# LIN_Interceptor_Board_EasyEDA_Pro.net
KiCad netlist of a schematic drawn in EasyEDA Pro
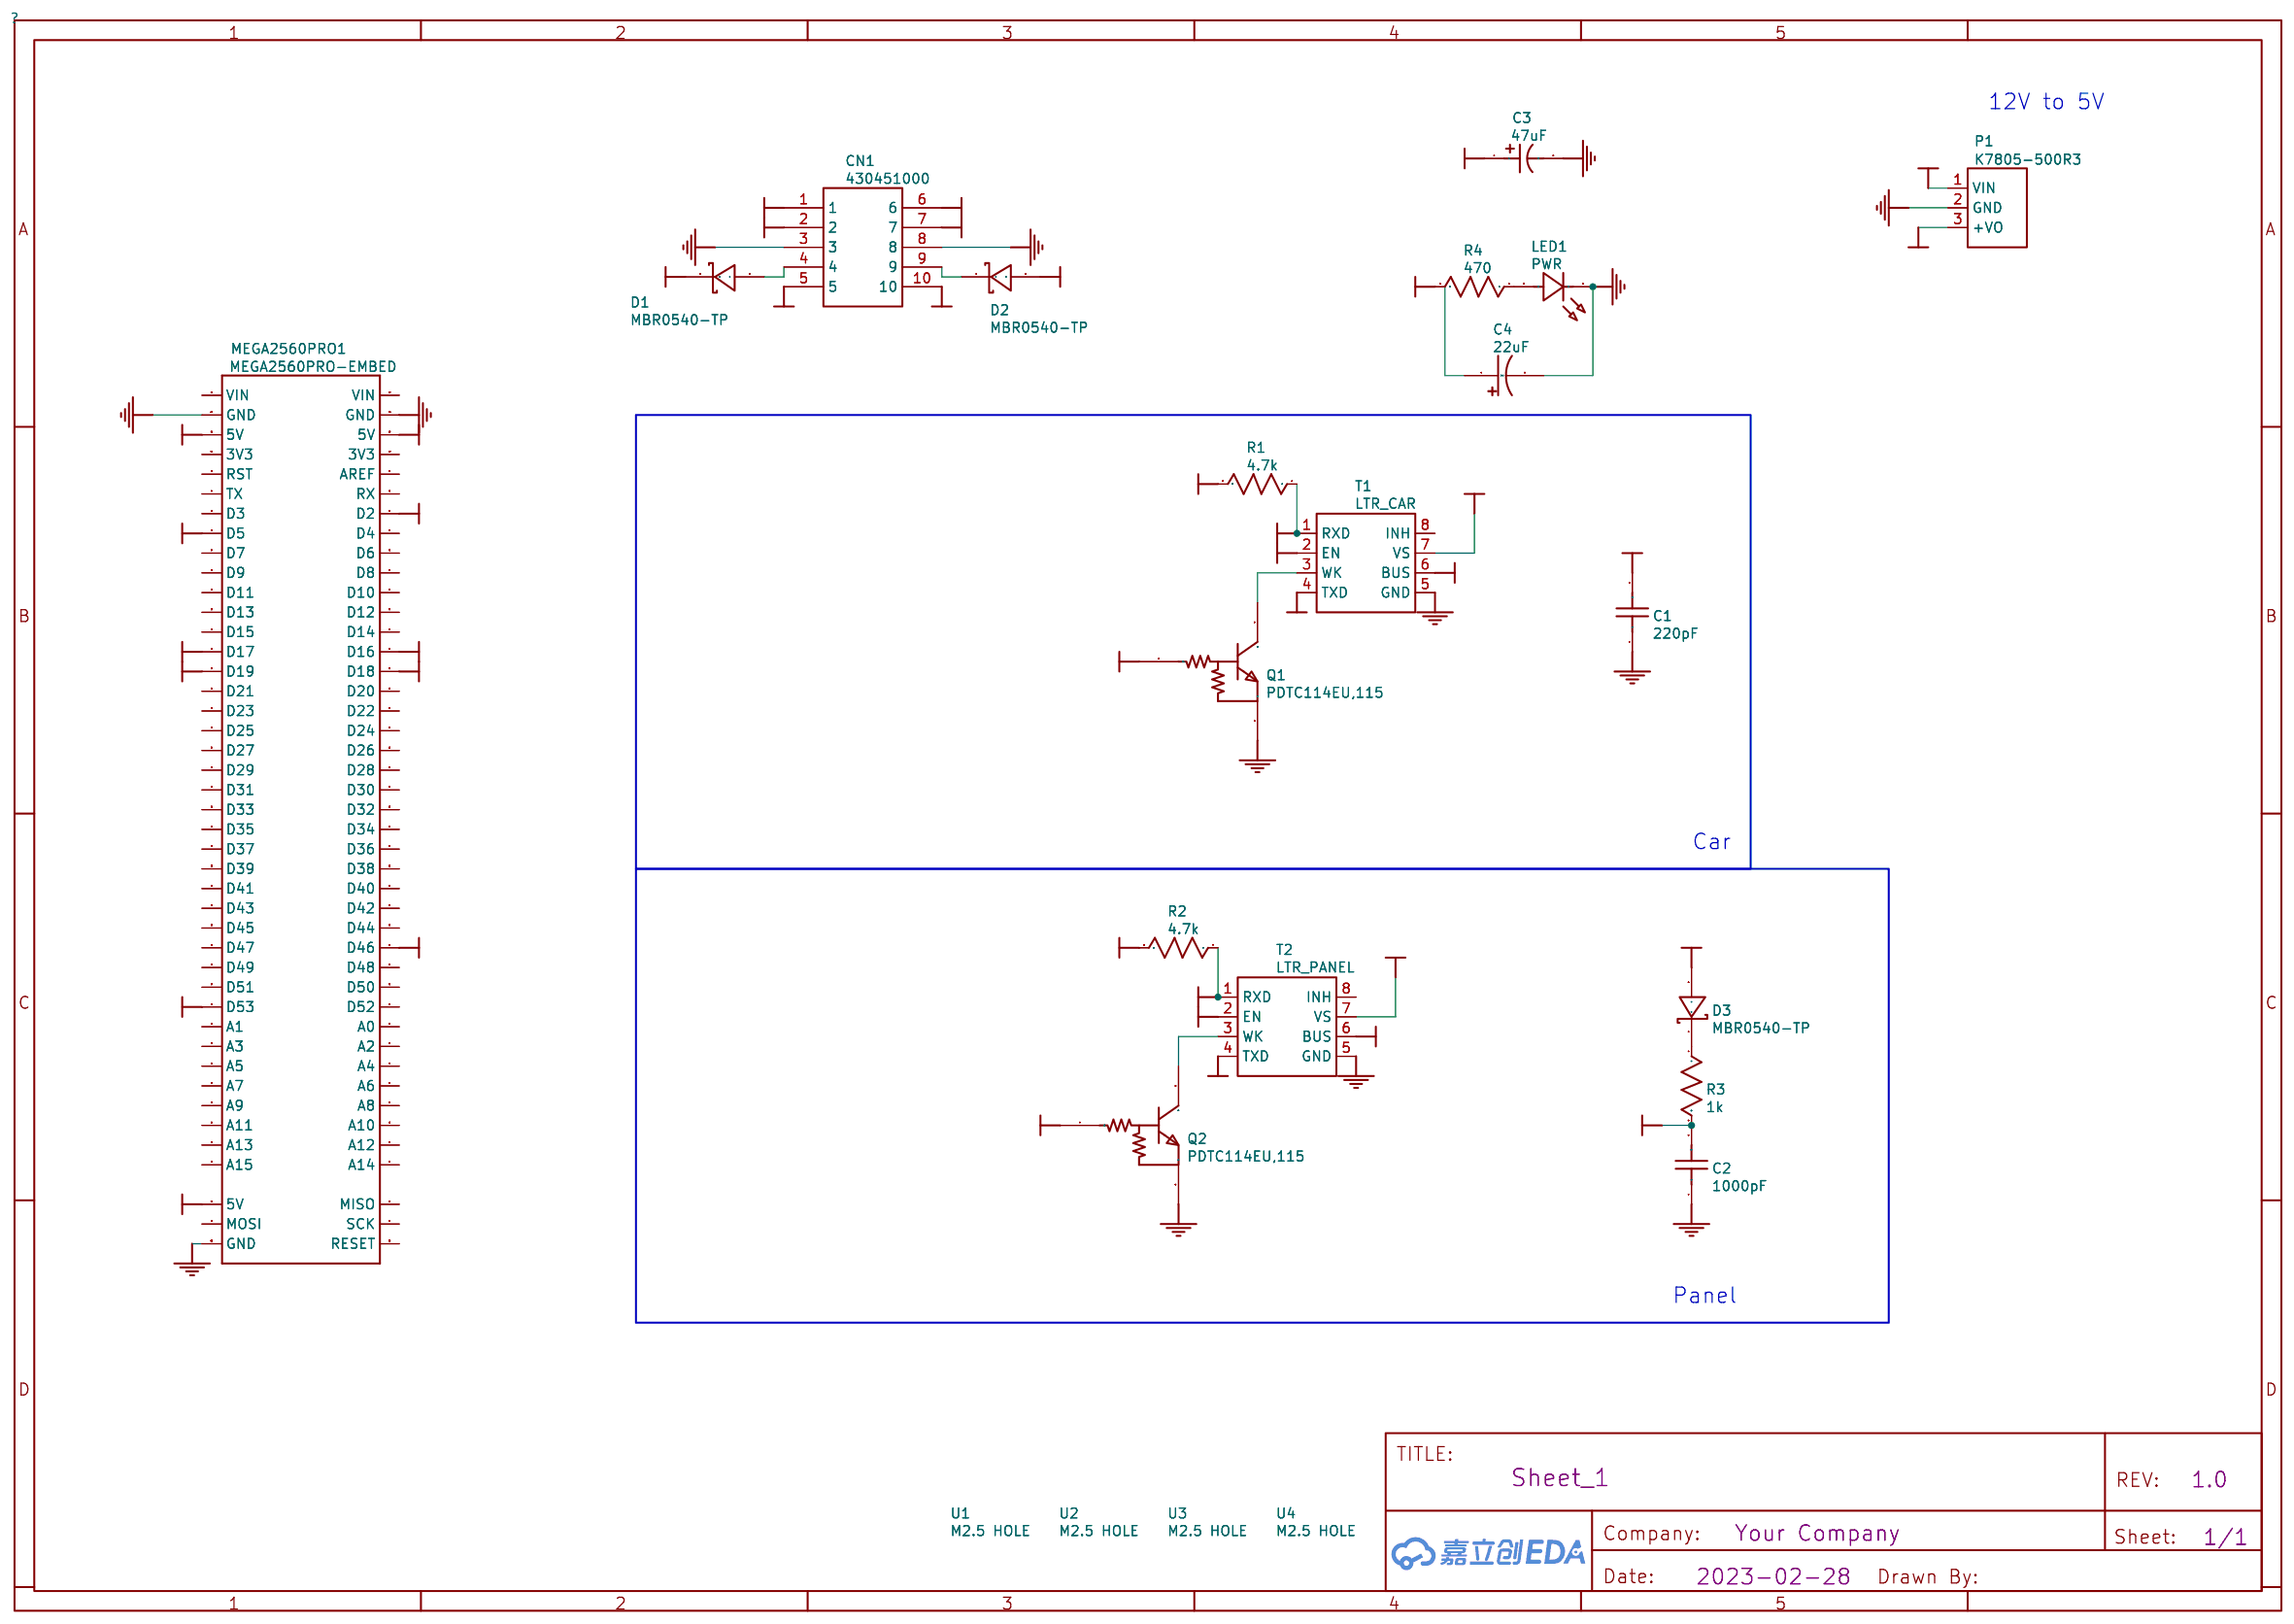
[diagram p0: schematic sheet]

(export (version "E")
  (design (tool "Eeschema 10.0.6"))
  (components
    (comp (ref "C1")
      (value "220pF")
      (footprint "easyedapro:C0603")
      (fields (field (name "Contributor") "LCEDA_Lib"))
      (libsource (lib "easyedapro") (part "220pF"))
    )
    (comp (ref "C2")
      (value "1000pF")
      (footprint "easyedapro:C0603")
      (fields (field (name "Contributor") "LCEDA_Lib"))
      (libsource (lib "easyedapro") (part "1000pF"))
    )
    (comp (ref "C3")
      (value "47uF")
      (footprint "easyedapro:CAP-SMD_BD6.3-L6.6-W6.6-LS7.3-FD")
      (fields
        (field (name "Manufacturer Part") "XT47UF50V90RV0082")
        (field (name "Manufacturer") "KNSCHA(科尼盛)")
        (field (name "Contributor") "lcsc")
      )
      (libsource (lib "easyedapro") (part "47uF"))
    )
    (comp (ref "C4")
      (value "22uF")
      (footprint "easyedapro:CAP-SMD_BD4.0-L4.3-W4.3-LS5.3-FD")
      (fields
        (field (name "Manufacturer Part") "RVT1A220M0405")
        (field (name "Manufacturer") "ROQANG(容强)")
        (field (name "Contributor") "LCSC")
      )
      (libsource (lib "easyedapro") (part "22uF"))
    )
    (comp (ref "CN1")
      (value "430451000")
      (footprint "easyedapro:CONN-TH_43045-1000")
      (fields (field (name "Manufacturer") "MOLEX"))
      (libsource (lib "easyedapro") (part "430451000"))
    )
    (comp (ref "D1")
      (value "MBR0540-TP")
      (footprint "easyedapro:SOD-123_L2.7-W1.6-LS3.7-RD")
      (fields (field (name "Manufacturer") "MCC(美微科)") (field (name "Contributor") "LCSC"))
      (libsource (lib "easyedapro") (part "MBR0540-TP"))
    )
    (comp (ref "D2")
      (value "MBR0540-TP")
      (footprint "easyedapro:SOD-123_L2.7-W1.6-LS3.7-RD")
      (fields (field (name "Manufacturer") "MCC(美微科)") (field (name "Contributor") "LCSC"))
      (libsource (lib "easyedapro") (part "MBR0540-TP"))
    )
    (comp (ref "D3")
      (value "MBR0540-TP")
      (footprint "easyedapro:SOD-123_L2.7-W1.6-LS3.7-RD")
      (fields (field (name "Manufacturer") "MCC(美微科)") (field (name "Contributor") "LCSC"))
      (libsource (lib "easyedapro") (part "MBR0540-TP"))
    )
    (comp (ref "LED1")
      (value "PWR")
      (footprint "easyedapro:LED0603-RD_RED")
      (fields
        (field (name "Manufacturer Part") "L-C191MJRCT")
        (field (name "Manufacturer") "PARALIGHT(光鼎)")
        (field (name "Contributor") "lcsc")
      )
      (libsource (lib "easyedapro") (part "PWR"))
    )
    (comp (ref "MEGA2560PRO1")
      (value "MEGA2560PRO-EMBED")
      (footprint "easyedapro:MEGA2560PRO-EMBED")
      (fields (field (name "Contributor") "Norseni"))
      (libsource (lib "easyedapro") (part "MEGA2560PRO-EMBED"))
    )
    (comp (ref "P1")
      (value "K7805-500R3")
      (footprint "easyedapro:PWRM-TH_K78XX-500R3")
      (fields (field (name "Manufacturer") "MORNSUN(金升阳)"))
      (libsource (lib "easyedapro") (part "K7805-500R3"))
    )
    (comp (ref "Q1")
      (value "PDTC114EU,115")
      (footprint "easyedapro:SOT-323-3_L2.0-W1.3-P1.30-LS2.1-BR")
      (fields (field (name "Manufacturer") "Nexperia(安世)"))
      (libsource (lib "easyedapro") (part "PDTC114EU,115"))
    )
    (comp (ref "Q2")
      (value "PDTC114EU,115")
      (footprint "easyedapro:SOT-323-3_L2.0-W1.3-P1.30-LS2.1-BR")
      (fields (field (name "Manufacturer") "Nexperia(安世)"))
      (libsource (lib "easyedapro") (part "PDTC114EU,115"))
    )
    (comp (ref "R1")
      (value "4.7k")
      (footprint "easyedapro:R0603")
      (fields (field (name "Contributor") "LCEDA_Lib"))
      (libsource (lib "easyedapro") (part "4.7k"))
    )
    (comp (ref "R2")
      (value "4.7k")
      (footprint "easyedapro:R0603")
      (fields (field (name "Contributor") "LCEDA_Lib"))
      (libsource (lib "easyedapro") (part "4.7k"))
    )
    (comp (ref "R3")
      (value "1k")
      (footprint "easyedapro:R0603")
      (fields (field (name "Contributor") "LCEDA_Lib"))
      (libsource (lib "easyedapro") (part "1k"))
    )
    (comp (ref "R4")
      (value "470")
      (footprint "easyedapro:R0603")
      (fields (field (name "Contributor") "LCEDA_Lib"))
      (libsource (lib "easyedapro") (part "470"))
    )
    (comp (ref "T1")
      (value "LTR_CAR")
      (footprint "easyedapro:PG-DSO-8_L5.0-W4.0-P1.27-LS6.0-BL")
      (fields
        (field (name "Manufacturer Part") "TLE7259-3GE")
        (field (name "Manufacturer") "Infineon(英飞凌)")
        (field (name "Contributor") "LCSC")
      )
      (libsource (lib "easyedapro") (part "LTR_CAR"))
    )
    (comp (ref "T2")
      (value "LTR_PANEL")
      (footprint "easyedapro:PG-DSO-8_L5.0-W4.0-P1.27-LS6.0-BL")
      (fields
        (field (name "Manufacturer Part") "TLE7259-3GE")
        (field (name "Manufacturer") "Infineon(英飞凌)")
        (field (name "Contributor") "LCSC")
      )
      (libsource (lib "easyedapro") (part "LTR_PANEL"))
    )
    (comp (ref "U1")
      (value "M2.5 HOLE")
      (footprint "easyedapro:HOLE_2.5MM_SCREW")
      (fields (field (name "Contributor") "dwalker"))
      (libsource (lib "easyedapro") (part "M2.5 HOLE"))
    )
    (comp (ref "U2")
      (value "M2.5 HOLE")
      (footprint "easyedapro:HOLE_2.5MM_SCREW")
      (fields (field (name "Contributor") "dwalker"))
      (libsource (lib "easyedapro") (part "M2.5 HOLE"))
    )
    (comp (ref "U3")
      (value "M2.5 HOLE")
      (footprint "easyedapro:HOLE_2.5MM_SCREW")
      (fields (field (name "Contributor") "dwalker"))
      (libsource (lib "easyedapro") (part "M2.5 HOLE"))
    )
    (comp (ref "U4")
      (value "M2.5 HOLE")
      (footprint "easyedapro:HOLE_2.5MM_SCREW")
      (fields (field (name "Contributor") "dwalker"))
      (libsource (lib "easyedapro") (part "M2.5 HOLE"))
    )
  )
  (nets
    (net (code "1") (name "+5V") (class "Default")
      (node (ref "MEGA2560PRO1") (pin "5V@1") (pinfunction "5V_5V@1") (pintype "bidirectional"))
      (node (ref "MEGA2560PRO1") (pin "5V@2") (pinfunction "5V_5V@2") (pintype "bidirectional"))
      (node (ref "MEGA2560PRO1") (pin "5V@3") (pinfunction "5V_5V@3") (pintype "bidirectional"))
      (node (ref "P1") (pin "3") (pinfunction "+VO_3") (pintype "unspecified"))
      (node (ref "R1") (pin "2") (pinfunction "2_2") (pintype "unspecified"))
      (node (ref "R2") (pin "2") (pinfunction "2_2") (pintype "unspecified"))
      (node (ref "R4") (pin "2") (pinfunction "2_2") (pintype "unspecified"))
    )
    (net (code "2") (name "+12V") (class "Default")
      (node (ref "C3") (pin "1") (pinfunction "1_1") (pintype "input"))
      (node (ref "D1") (pin "1") (pinfunction "K_1") (pintype "unspecified"))
      (node (ref "D2") (pin "2") (pinfunction "A_2") (pintype "unspecified"))
      (node (ref "D3") (pin "2") (pinfunction "A_2") (pintype "unspecified"))
      (node (ref "P1") (pin "1") (pinfunction "VIN_1") (pintype "unspecified"))
      (node (ref "T1") (pin "7") (pinfunction "VS_7") (pintype "unspecified"))
      (node (ref "T2") (pin "7") (pinfunction "VS_7") (pintype "unspecified"))
    )
    (net (code "3") (name "+ILLUM") (class "Default")
      (node (ref "CN1") (pin "10") (pinfunction "10_10") (pintype "unspecified"))
      (node (ref "CN1") (pin "5") (pinfunction "5_5") (pintype "unspecified"))
    )
    (net (code "4") (name "-ILLUM") (class "Default")
      (node (ref "CN1") (pin "2") (pinfunction "2_2") (pintype "unspecified"))
      (node (ref "CN1") (pin "7") (pinfunction "7_7") (pintype "unspecified"))
    )
    (net (code "5") (name "EN1") (class "Default")
      (node (ref "MEGA2560PRO1") (pin "D53") (pinfunction "D53_D53") (pintype "bidirectional"))
      (node (ref "T1") (pin "2") (pinfunction "EN_2") (pintype "unspecified"))
    )
    (net (code "6") (name "EN2") (class "Default")
      (node (ref "MEGA2560PRO1") (pin "D46") (pinfunction "D46_D46") (pintype "bidirectional"))
      (node (ref "T2") (pin "2") (pinfunction "EN_2") (pintype "unspecified"))
    )
    (net (code "7") (name "GND") (class "Default")
      (node (ref "C1") (pin "1") (pinfunction "1_1") (pintype "unspecified"))
      (node (ref "C2") (pin "1") (pinfunction "1_1") (pintype "unspecified"))
      (node (ref "C3") (pin "2") (pinfunction "2_2") (pintype "input"))
      (node (ref "C4") (pin "2") (pinfunction "2_2") (pintype "unspecified"))
      (node (ref "CN1") (pin "3") (pinfunction "3_3") (pintype "unspecified"))
      (node (ref "CN1") (pin "8") (pinfunction "8_8") (pintype "unspecified"))
      (node (ref "LED1") (pin "1") (pinfunction "K_1") (pintype "unspecified"))
      (node (ref "MEGA2560PRO1") (pin "GND@1") (pinfunction "GND_GND@1") (pintype "bidirectional"))
      (node (ref "MEGA2560PRO1") (pin "GND@2") (pinfunction "GND_GND@2") (pintype "bidirectional"))
      (node (ref "MEGA2560PRO1") (pin "GND@3") (pinfunction "GND_GND@3") (pintype "bidirectional"))
      (node (ref "P1") (pin "2") (pinfunction "GND_2") (pintype "unspecified"))
      (node (ref "Q1") (pin "2") (pinfunction "E_2") (pintype "unspecified"))
      (node (ref "Q2") (pin "2") (pinfunction "E_2") (pintype "unspecified"))
      (node (ref "T1") (pin "5") (pinfunction "GND_5") (pintype "unspecified"))
      (node (ref "T2") (pin "5") (pinfunction "GND_5") (pintype "unspecified"))
    )
    (net (code "8") (name "LIN_CAR") (class "Default")
      (node (ref "C1") (pin "2") (pinfunction "2_2") (pintype "unspecified"))
      (node (ref "CN1") (pin "1") (pinfunction "1_1") (pintype "unspecified"))
      (node (ref "T1") (pin "6") (pinfunction "BUS_6") (pintype "unspecified"))
    )
    (net (code "9") (name "LIN_PANEL") (class "Default")
      (node (ref "C2") (pin "2") (pinfunction "2_2") (pintype "unspecified"))
      (node (ref "CN1") (pin "6") (pinfunction "6_6") (pintype "unspecified"))
      (node (ref "R3") (pin "2") (pinfunction "2_2") (pintype "unspecified"))
      (node (ref "T2") (pin "6") (pinfunction "BUS_6") (pintype "unspecified"))
    )
    (net (code "10") (name "Net-(D1-A)") (class "Default")
      (node (ref "CN1") (pin "4") (pinfunction "4_4") (pintype "unspecified"))
      (node (ref "D1") (pin "2") (pinfunction "A_2") (pintype "unspecified"))
    )
    (net (code "11") (name "Net-(D2-K)") (class "Default")
      (node (ref "CN1") (pin "9") (pinfunction "9_9") (pintype "unspecified"))
      (node (ref "D2") (pin "1") (pinfunction "K_1") (pintype "unspecified"))
    )
    (net (code "12") (name "Net-(D3-K)") (class "Default")
      (node (ref "D3") (pin "1") (pinfunction "K_1") (pintype "unspecified"))
      (node (ref "R3") (pin "1") (pinfunction "1_1") (pintype "unspecified"))
    )
    (net (code "13") (name "Net-(LED1-A)") (class "Default")
      (node (ref "LED1") (pin "2") (pinfunction "A_2") (pintype "unspecified"))
      (node (ref "R4") (pin "1") (pinfunction "1_1") (pintype "unspecified"))
    )
    (net (code "14") (name "Net-(Q1-C)") (class "Default")
      (node (ref "Q1") (pin "3") (pinfunction "C_3") (pintype "unspecified"))
      (node (ref "T1") (pin "3") (pinfunction "WK_3") (pintype "unspecified"))
    )
    (net (code "15") (name "Net-(Q2-C)") (class "Default")
      (node (ref "Q2") (pin "3") (pinfunction "C_3") (pintype "unspecified"))
      (node (ref "T2") (pin "3") (pinfunction "WK_3") (pintype "unspecified"))
    )
    (net (code "16") (name "RX1") (class "Default")
      (node (ref "MEGA2560PRO1") (pin "D19") (pinfunction "D19_D19") (pintype "bidirectional"))
      (node (ref "R1") (pin "1") (pinfunction "1_1") (pintype "unspecified"))
      (node (ref "T1") (pin "1") (pinfunction "RXD_1") (pintype "unspecified"))
    )
    (net (code "17") (name "RX2") (class "Default")
      (node (ref "MEGA2560PRO1") (pin "D17") (pinfunction "D17_D17") (pintype "bidirectional"))
      (node (ref "R2") (pin "1") (pinfunction "1_1") (pintype "unspecified"))
      (node (ref "T2") (pin "1") (pinfunction "RXD_1") (pintype "unspecified"))
    )
    (net (code "18") (name "TX1") (class "Default")
      (node (ref "MEGA2560PRO1") (pin "D18") (pinfunction "D18_D18") (pintype "bidirectional"))
      (node (ref "T1") (pin "4") (pinfunction "TXD_4") (pintype "unspecified"))
    )
    (net (code "19") (name "TX2") (class "Default")
      (node (ref "MEGA2560PRO1") (pin "D16") (pinfunction "D16_D16") (pintype "bidirectional"))
      (node (ref "T2") (pin "4") (pinfunction "TXD_4") (pintype "unspecified"))
    )
    (net (code "20") (name "WK1") (class "Default")
      (node (ref "MEGA2560PRO1") (pin "D5") (pinfunction "D5_D5") (pintype "bidirectional"))
      (node (ref "Q1") (pin "1") (pinfunction "B_1") (pintype "unspecified"))
    )
    (net (code "21") (name "WK2") (class "Default")
      (node (ref "MEGA2560PRO1") (pin "D2") (pinfunction "D2_D2") (pintype "bidirectional"))
      (node (ref "Q2") (pin "1") (pinfunction "B_1") (pintype "unspecified"))
    )
    (net (code "22") (name "unconnected-(C4-Pad1)") (class "Default")
      (node (ref "C4") (pin "1") (pinfunction "1_1") (pintype "unspecified"))
    )
    (net (code "23") (name "unconnected-(MEGA2560PRO1-3V3-Pad3V3@1)") (class "Default")
      (node (ref "MEGA2560PRO1") (pin "3V3@1") (pinfunction "3V3_3V3@1") (pintype "bidirectional"))
    )
    (net (code "24") (name "unconnected-(MEGA2560PRO1-3V3-Pad3V3@2)") (class "Default")
      (node (ref "MEGA2560PRO1") (pin "3V3@2") (pinfunction "3V3_3V3@2") (pintype "bidirectional"))
    )
    (net (code "25") (name "unconnected-(MEGA2560PRO1-PadA0)") (class "Default")
      (node (ref "MEGA2560PRO1") (pin "A0") (pinfunction "A0_A0") (pintype "bidirectional"))
    )
    (net (code "26") (name "unconnected-(MEGA2560PRO1-PadA1)") (class "Default")
      (node (ref "MEGA2560PRO1") (pin "A1") (pinfunction "A1_A1") (pintype "bidirectional"))
    )
    (net (code "27") (name "unconnected-(MEGA2560PRO1-PadA2)") (class "Default")
      (node (ref "MEGA2560PRO1") (pin "A2") (pinfunction "A2_A2") (pintype "bidirectional"))
    )
    (net (code "28") (name "unconnected-(MEGA2560PRO1-PadA3)") (class "Default")
      (node (ref "MEGA2560PRO1") (pin "A3") (pinfunction "A3_A3") (pintype "bidirectional"))
    )
    (net (code "29") (name "unconnected-(MEGA2560PRO1-PadA4)") (class "Default")
      (node (ref "MEGA2560PRO1") (pin "A4") (pinfunction "A4_A4") (pintype "bidirectional"))
    )
    (net (code "30") (name "unconnected-(MEGA2560PRO1-PadA5)") (class "Default")
      (node (ref "MEGA2560PRO1") (pin "A5") (pinfunction "A5_A5") (pintype "bidirectional"))
    )
    (net (code "31") (name "unconnected-(MEGA2560PRO1-PadA6)") (class "Default")
      (node (ref "MEGA2560PRO1") (pin "A6") (pinfunction "A6_A6") (pintype "bidirectional"))
    )
    (net (code "32") (name "unconnected-(MEGA2560PRO1-PadA7)") (class "Default")
      (node (ref "MEGA2560PRO1") (pin "A7") (pinfunction "A7_A7") (pintype "bidirectional"))
    )
    (net (code "33") (name "unconnected-(MEGA2560PRO1-PadA8)") (class "Default")
      (node (ref "MEGA2560PRO1") (pin "A8") (pinfunction "A8_A8") (pintype "bidirectional"))
    )
    (net (code "34") (name "unconnected-(MEGA2560PRO1-PadA9)") (class "Default")
      (node (ref "MEGA2560PRO1") (pin "A9") (pinfunction "A9_A9") (pintype "bidirectional"))
    )
    (net (code "35") (name "unconnected-(MEGA2560PRO1-PadA10)") (class "Default")
      (node (ref "MEGA2560PRO1") (pin "A10") (pinfunction "A10_A10") (pintype "bidirectional"))
    )
    (net (code "36") (name "unconnected-(MEGA2560PRO1-PadA11)") (class "Default")
      (node (ref "MEGA2560PRO1") (pin "A11") (pinfunction "A11_A11") (pintype "bidirectional"))
    )
    (net (code "37") (name "unconnected-(MEGA2560PRO1-PadA12)") (class "Default")
      (node (ref "MEGA2560PRO1") (pin "A12") (pinfunction "A12_A12") (pintype "bidirectional"))
    )
    (net (code "38") (name "unconnected-(MEGA2560PRO1-PadA13)") (class "Default")
      (node (ref "MEGA2560PRO1") (pin "A13") (pinfunction "A13_A13") (pintype "bidirectional"))
    )
    (net (code "39") (name "unconnected-(MEGA2560PRO1-PadA14)") (class "Default")
      (node (ref "MEGA2560PRO1") (pin "A14") (pinfunction "A14_A14") (pintype "bidirectional"))
    )
    (net (code "40") (name "unconnected-(MEGA2560PRO1-PadA15)") (class "Default")
      (node (ref "MEGA2560PRO1") (pin "A15") (pinfunction "A15_A15") (pintype "bidirectional"))
    )
    (net (code "41") (name "unconnected-(MEGA2560PRO1-PadAREF)") (class "Default")
      (node (ref "MEGA2560PRO1") (pin "AREF") (pinfunction "AREF_AREF") (pintype "bidirectional"))
    )
    (net (code "42") (name "unconnected-(MEGA2560PRO1-PadD3)") (class "Default")
      (node (ref "MEGA2560PRO1") (pin "D3") (pinfunction "D3_D3") (pintype "bidirectional"))
    )
    (net (code "43") (name "unconnected-(MEGA2560PRO1-PadD4)") (class "Default")
      (node (ref "MEGA2560PRO1") (pin "D4") (pinfunction "D4_D4") (pintype "bidirectional"))
    )
    (net (code "44") (name "unconnected-(MEGA2560PRO1-PadD6)") (class "Default")
      (node (ref "MEGA2560PRO1") (pin "D6") (pinfunction "D6_D6") (pintype "bidirectional"))
    )
    (net (code "45") (name "unconnected-(MEGA2560PRO1-PadD7)") (class "Default")
      (node (ref "MEGA2560PRO1") (pin "D7") (pinfunction "D7_D7") (pintype "bidirectional"))
    )
    (net (code "46") (name "unconnected-(MEGA2560PRO1-PadD8)") (class "Default")
      (node (ref "MEGA2560PRO1") (pin "D8") (pinfunction "D8_D8") (pintype "bidirectional"))
    )
    (net (code "47") (name "unconnected-(MEGA2560PRO1-PadD9)") (class "Default")
      (node (ref "MEGA2560PRO1") (pin "D9") (pinfunction "D9_D9") (pintype "bidirectional"))
    )
    (net (code "48") (name "unconnected-(MEGA2560PRO1-PadD10)") (class "Default")
      (node (ref "MEGA2560PRO1") (pin "D10") (pinfunction "D10_D10") (pintype "bidirectional"))
    )
    (net (code "49") (name "unconnected-(MEGA2560PRO1-PadD11)") (class "Default")
      (node (ref "MEGA2560PRO1") (pin "D11") (pinfunction "D11_D11") (pintype "bidirectional"))
    )
    (net (code "50") (name "unconnected-(MEGA2560PRO1-PadD12)") (class "Default")
      (node (ref "MEGA2560PRO1") (pin "D12") (pinfunction "D12_D12") (pintype "bidirectional"))
    )
    (net (code "51") (name "unconnected-(MEGA2560PRO1-PadD13)") (class "Default")
      (node (ref "MEGA2560PRO1") (pin "D13") (pinfunction "D13_D13") (pintype "bidirectional"))
    )
    (net (code "52") (name "unconnected-(MEGA2560PRO1-PadD14)") (class "Default")
      (node (ref "MEGA2560PRO1") (pin "D14") (pinfunction "D14_D14") (pintype "bidirectional"))
    )
    (net (code "53") (name "unconnected-(MEGA2560PRO1-PadD15)") (class "Default")
      (node (ref "MEGA2560PRO1") (pin "D15") (pinfunction "D15_D15") (pintype "bidirectional"))
    )
    (net (code "54") (name "unconnected-(MEGA2560PRO1-PadD20)") (class "Default")
      (node (ref "MEGA2560PRO1") (pin "D20") (pinfunction "D20_D20") (pintype "bidirectional"))
    )
    (net (code "55") (name "unconnected-(MEGA2560PRO1-PadD21)") (class "Default")
      (node (ref "MEGA2560PRO1") (pin "D21") (pinfunction "D21_D21") (pintype "bidirectional"))
    )
    (net (code "56") (name "unconnected-(MEGA2560PRO1-PadD22)") (class "Default")
      (node (ref "MEGA2560PRO1") (pin "D22") (pinfunction "D22_D22") (pintype "bidirectional"))
    )
    (net (code "57") (name "unconnected-(MEGA2560PRO1-PadD23)") (class "Default")
      (node (ref "MEGA2560PRO1") (pin "D23") (pinfunction "D23_D23") (pintype "bidirectional"))
    )
    (net (code "58") (name "unconnected-(MEGA2560PRO1-PadD24)") (class "Default")
      (node (ref "MEGA2560PRO1") (pin "D24") (pinfunction "D24_D24") (pintype "bidirectional"))
    )
    (net (code "59") (name "unconnected-(MEGA2560PRO1-PadD25)") (class "Default")
      (node (ref "MEGA2560PRO1") (pin "D25") (pinfunction "D25_D25") (pintype "bidirectional"))
    )
    (net (code "60") (name "unconnected-(MEGA2560PRO1-PadD26)") (class "Default")
      (node (ref "MEGA2560PRO1") (pin "D26") (pinfunction "D26_D26") (pintype "bidirectional"))
    )
    (net (code "61") (name "unconnected-(MEGA2560PRO1-PadD27)") (class "Default")
      (node (ref "MEGA2560PRO1") (pin "D27") (pinfunction "D27_D27") (pintype "bidirectional"))
    )
    (net (code "62") (name "unconnected-(MEGA2560PRO1-PadD28)") (class "Default")
      (node (ref "MEGA2560PRO1") (pin "D28") (pinfunction "D28_D28") (pintype "bidirectional"))
    )
    (net (code "63") (name "unconnected-(MEGA2560PRO1-PadD29)") (class "Default")
      (node (ref "MEGA2560PRO1") (pin "D29") (pinfunction "D29_D29") (pintype "bidirectional"))
    )
    (net (code "64") (name "unconnected-(MEGA2560PRO1-PadD30)") (class "Default")
      (node (ref "MEGA2560PRO1") (pin "D30") (pinfunction "D30_D30") (pintype "bidirectional"))
    )
    (net (code "65") (name "unconnected-(MEGA2560PRO1-PadD31)") (class "Default")
      (node (ref "MEGA2560PRO1") (pin "D31") (pinfunction "D31_D31") (pintype "bidirectional"))
    )
    (net (code "66") (name "unconnected-(MEGA2560PRO1-PadD32)") (class "Default")
      (node (ref "MEGA2560PRO1") (pin "D32") (pinfunction "D32_D32") (pintype "bidirectional"))
    )
    (net (code "67") (name "unconnected-(MEGA2560PRO1-PadD33)") (class "Default")
      (node (ref "MEGA2560PRO1") (pin "D33") (pinfunction "D33_D33") (pintype "bidirectional"))
    )
    (net (code "68") (name "unconnected-(MEGA2560PRO1-PadD34)") (class "Default")
      (node (ref "MEGA2560PRO1") (pin "D34") (pinfunction "D34_D34") (pintype "bidirectional"))
    )
    (net (code "69") (name "unconnected-(MEGA2560PRO1-PadD35)") (class "Default")
      (node (ref "MEGA2560PRO1") (pin "D35") (pinfunction "D35_D35") (pintype "bidirectional"))
    )
    (net (code "70") (name "unconnected-(MEGA2560PRO1-PadD36)") (class "Default")
      (node (ref "MEGA2560PRO1") (pin "D36") (pinfunction "D36_D36") (pintype "bidirectional"))
    )
    (net (code "71") (name "unconnected-(MEGA2560PRO1-PadD37)") (class "Default")
      (node (ref "MEGA2560PRO1") (pin "D37") (pinfunction "D37_D37") (pintype "bidirectional"))
    )
    (net (code "72") (name "unconnected-(MEGA2560PRO1-PadD38)") (class "Default")
      (node (ref "MEGA2560PRO1") (pin "D38") (pinfunction "D38_D38") (pintype "bidirectional"))
    )
    (net (code "73") (name "unconnected-(MEGA2560PRO1-PadD39)") (class "Default")
      (node (ref "MEGA2560PRO1") (pin "D39") (pinfunction "D39_D39") (pintype "bidirectional"))
    )
    (net (code "74") (name "unconnected-(MEGA2560PRO1-PadD40)") (class "Default")
      (node (ref "MEGA2560PRO1") (pin "D40") (pinfunction "D40_D40") (pintype "bidirectional"))
    )
    (net (code "75") (name "unconnected-(MEGA2560PRO1-PadD41)") (class "Default")
      (node (ref "MEGA2560PRO1") (pin "D41") (pinfunction "D41_D41") (pintype "bidirectional"))
    )
    (net (code "76") (name "unconnected-(MEGA2560PRO1-PadD42)") (class "Default")
      (node (ref "MEGA2560PRO1") (pin "D42") (pinfunction "D42_D42") (pintype "bidirectional"))
    )
    (net (code "77") (name "unconnected-(MEGA2560PRO1-PadD43)") (class "Default")
      (node (ref "MEGA2560PRO1") (pin "D43") (pinfunction "D43_D43") (pintype "bidirectional"))
    )
    (net (code "78") (name "unconnected-(MEGA2560PRO1-PadD44)") (class "Default")
      (node (ref "MEGA2560PRO1") (pin "D44") (pinfunction "D44_D44") (pintype "bidirectional"))
    )
    (net (code "79") (name "unconnected-(MEGA2560PRO1-PadD45)") (class "Default")
      (node (ref "MEGA2560PRO1") (pin "D45") (pinfunction "D45_D45") (pintype "bidirectional"))
    )
    (net (code "80") (name "unconnected-(MEGA2560PRO1-PadD47)") (class "Default")
      (node (ref "MEGA2560PRO1") (pin "D47") (pinfunction "D47_D47") (pintype "bidirectional"))
    )
    (net (code "81") (name "unconnected-(MEGA2560PRO1-PadD48)") (class "Default")
      (node (ref "MEGA2560PRO1") (pin "D48") (pinfunction "D48_D48") (pintype "bidirectional"))
    )
    (net (code "82") (name "unconnected-(MEGA2560PRO1-PadD49)") (class "Default")
      (node (ref "MEGA2560PRO1") (pin "D49") (pinfunction "D49_D49") (pintype "bidirectional"))
    )
    (net (code "83") (name "unconnected-(MEGA2560PRO1-PadD50)") (class "Default")
      (node (ref "MEGA2560PRO1") (pin "D50") (pinfunction "D50_D50") (pintype "bidirectional"))
    )
    (net (code "84") (name "unconnected-(MEGA2560PRO1-PadD51)") (class "Default")
      (node (ref "MEGA2560PRO1") (pin "D51") (pinfunction "D51_D51") (pintype "bidirectional"))
    )
    (net (code "85") (name "unconnected-(MEGA2560PRO1-PadD52)") (class "Default")
      (node (ref "MEGA2560PRO1") (pin "D52") (pinfunction "D52_D52") (pintype "bidirectional"))
    )
    (net (code "86") (name "unconnected-(MEGA2560PRO1-PadMISO)") (class "Default")
      (node (ref "MEGA2560PRO1") (pin "MISO") (pinfunction "MISO_MISO") (pintype "bidirectional"))
    )
    (net (code "87") (name "unconnected-(MEGA2560PRO1-PadMOSI)") (class "Default")
      (node (ref "MEGA2560PRO1") (pin "MOSI") (pinfunction "MOSI_MOSI") (pintype "bidirectional"))
    )
    (net (code "88") (name "unconnected-(MEGA2560PRO1-PadRESET)") (class "Default")
      (node (ref "MEGA2560PRO1") (pin "RESET") (pinfunction "RESET_RESET") (pintype "bidirectional"))
    )
    (net (code "89") (name "unconnected-(MEGA2560PRO1-PadRST)") (class "Default")
      (node (ref "MEGA2560PRO1") (pin "RST") (pinfunction "RST_RST") (pintype "bidirectional"))
    )
    (net (code "90") (name "unconnected-(MEGA2560PRO1-PadRX)") (class "Default")
      (node (ref "MEGA2560PRO1") (pin "RX") (pinfunction "RX_RX") (pintype "bidirectional"))
    )
    (net (code "91") (name "unconnected-(MEGA2560PRO1-PadSCK)") (class "Default")
      (node (ref "MEGA2560PRO1") (pin "SCK") (pinfunction "SCK_SCK") (pintype "bidirectional"))
    )
    (net (code "92") (name "unconnected-(MEGA2560PRO1-PadTX)") (class "Default")
      (node (ref "MEGA2560PRO1") (pin "TX") (pinfunction "TX_TX") (pintype "bidirectional"))
    )
    (net (code "93") (name "unconnected-(MEGA2560PRO1-VIN-PadVIN@1)") (class "Default")
      (node (ref "MEGA2560PRO1") (pin "VIN@1") (pinfunction "VIN_VIN@1") (pintype "bidirectional"))
    )
    (net (code "94") (name "unconnected-(MEGA2560PRO1-VIN-PadVIN@2)") (class "Default")
      (node (ref "MEGA2560PRO1") (pin "VIN@2") (pinfunction "VIN_VIN@2") (pintype "bidirectional"))
    )
    (net (code "95") (name "unconnected-(T1-INH-Pad8)") (class "Default")
      (node (ref "T1") (pin "8") (pinfunction "INH_8") (pintype "unspecified"))
    )
    (net (code "96") (name "unconnected-(T2-INH-Pad8)") (class "Default")
      (node (ref "T2") (pin "8") (pinfunction "INH_8") (pintype "unspecified"))
    )
  )
)
